# zeta2rework_lw_v27_rework.net
KiCad netlist of a schematic drawn in EAGLE
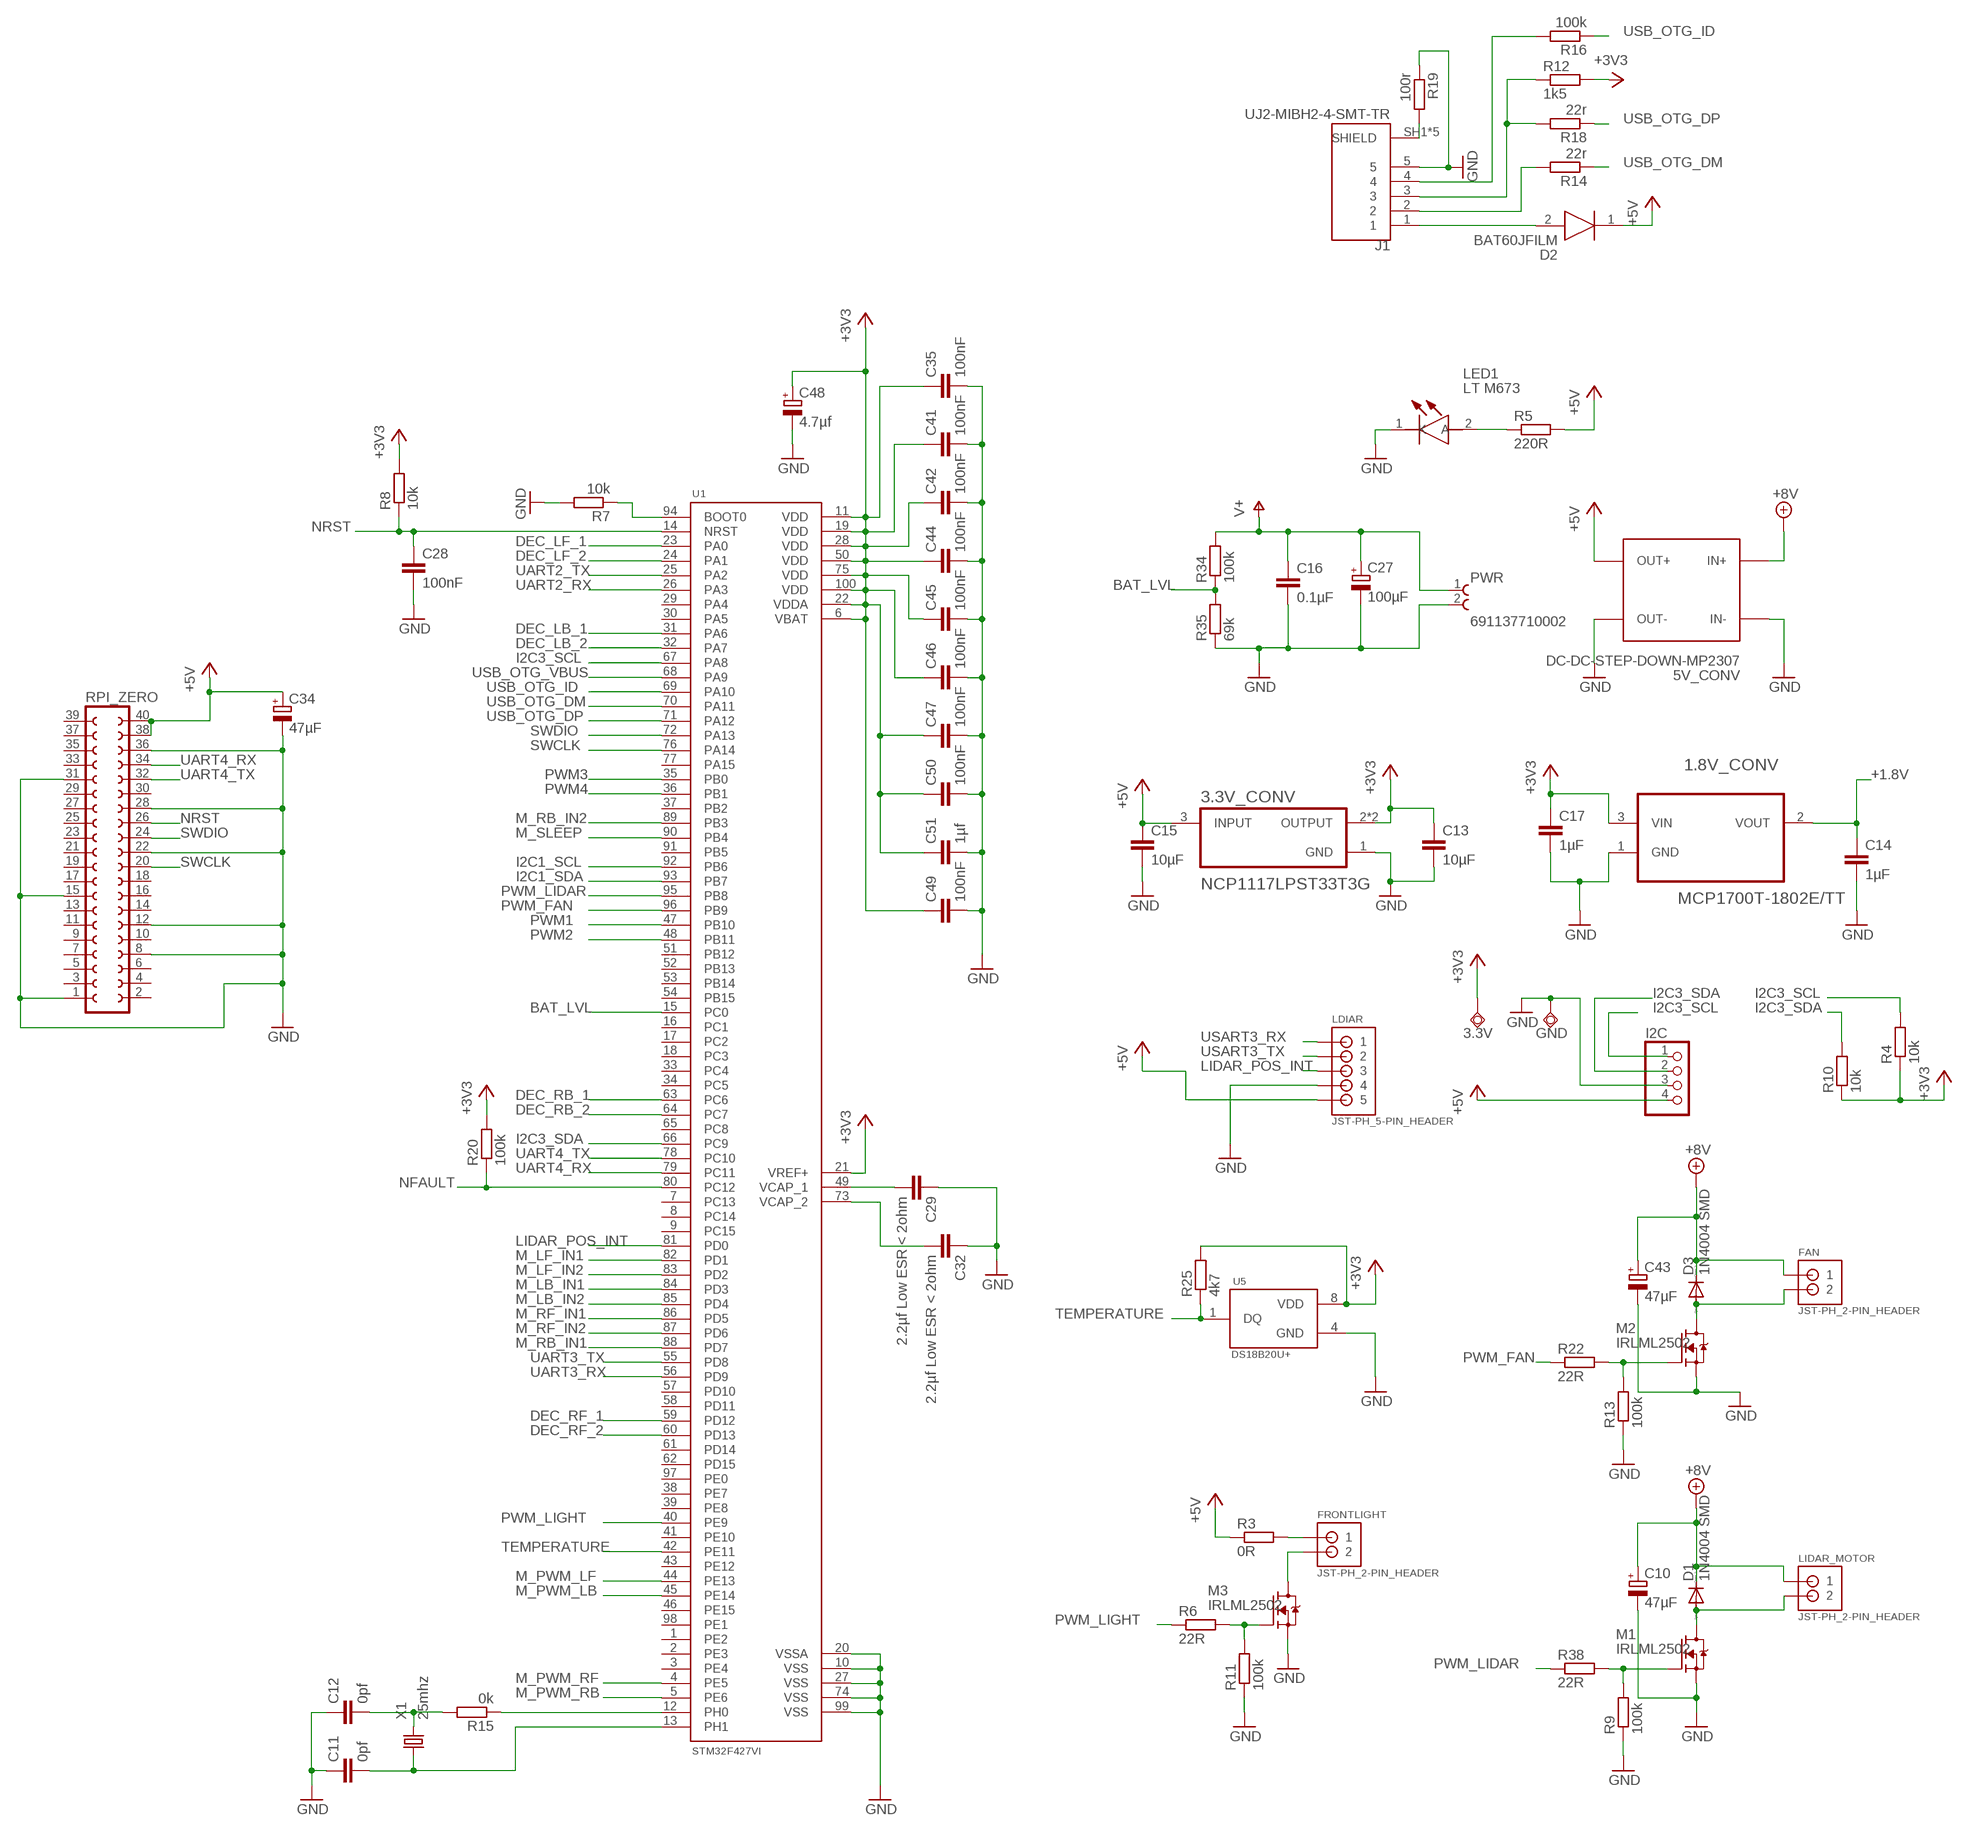
[diagram p0: schematic, sheet 1, part 1 of 2]
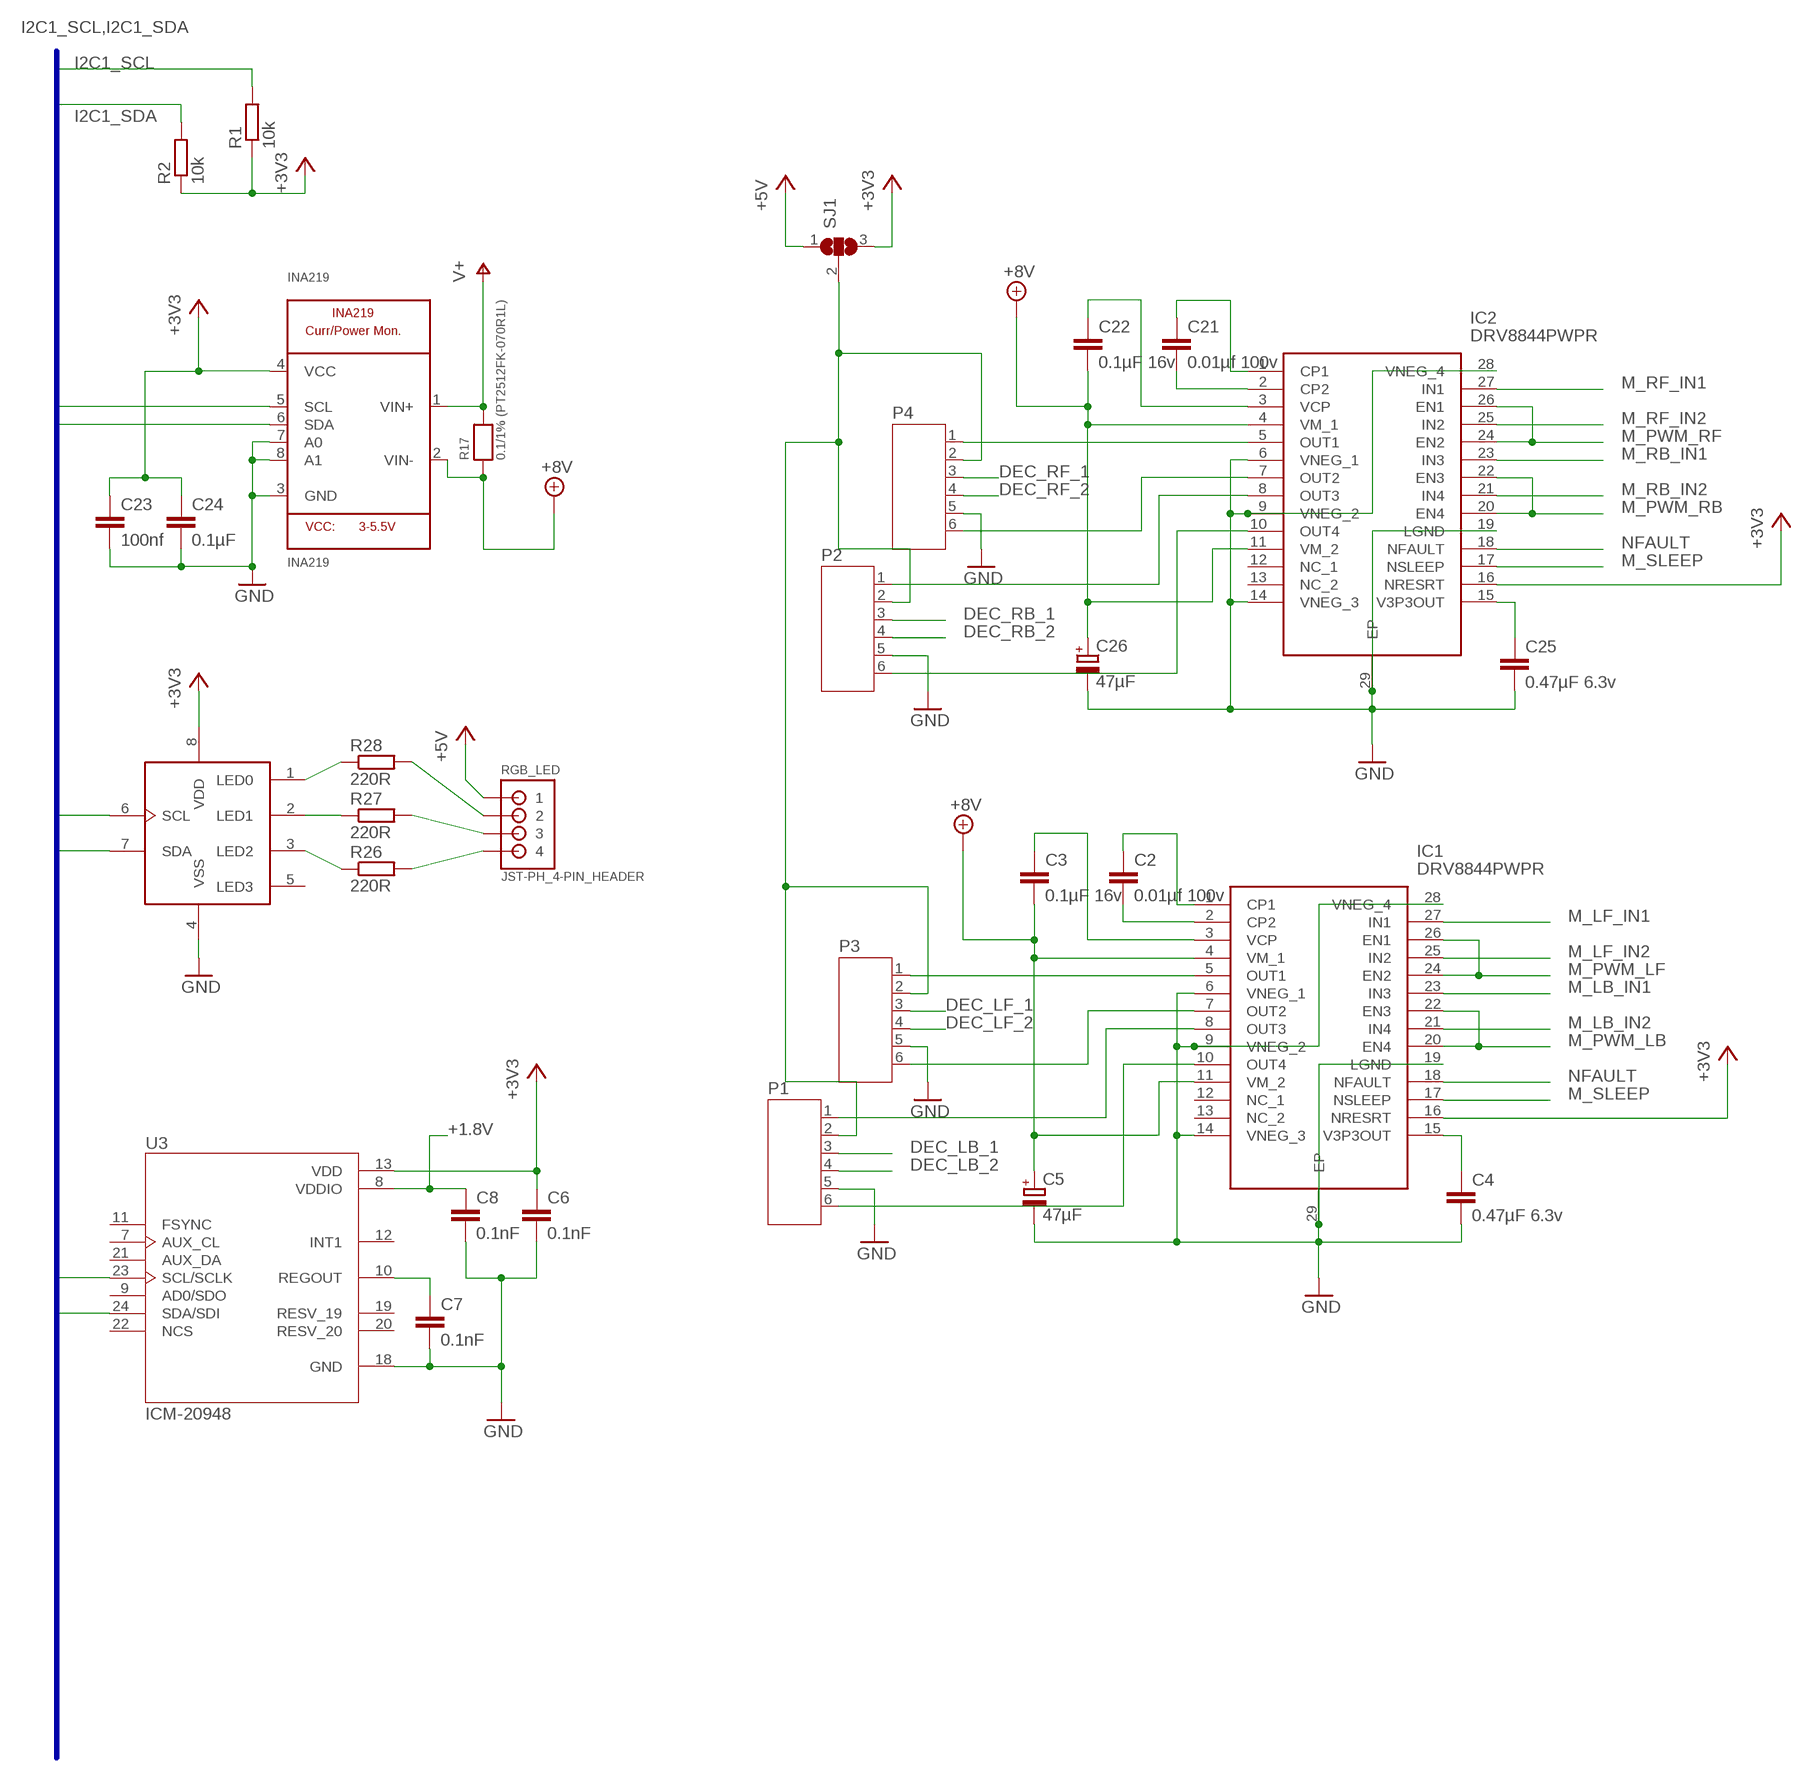
[diagram p1: schematic, sheet 1, part 2 of 2]

(export (version "E")
  (design (tool "Eeschema 10.0.6"))
  (components
    (comp (ref "1.8V_CONV")
      (value "MCP1700T-1802E/TT")
      (footprint "eagle-import:SOT95P237X112-3N")
      (fields (field (name "MF") "Microchip") (field (name "MP") "MCP1700T-2102E/TT"))
      (libsource (lib "eagle-import") (part "MCP1700T-2102E/TT"))
    )
    (comp (ref "3.3V")
      (value "TPSQTP20R")
      (footprint "eagle-import:TP20R")
      (libsource (lib "eagle-import") (part "TPSQTP20R"))
    )
    (comp (ref "3.3V_CONV")
      (value "NCP1117LPST33T3G")
      (footprint "eagle-import:SOT230P700X175-4N")
      (fields (field (name "MF") "ON Semiconductor"))
      (libsource (lib "eagle-import") (part "NCP1117LPST33T3G"))
    )
    (comp (ref "5V_CONV")
      (value "DC-DC-STEP-DOWN-MP2307")
      (footprint "eagle-import:DC-DC-STEP-DOWN-MP2307")
      (libsource (lib "eagle-import") (part "DC-DC-STEP-DOWN-MP2307"))
    )
    (comp (ref "C2")
      (value "0.01µf 100v")
      (footprint "eagle-import:C1206")
      (libsource (lib "eagle-import") (part "C-EUC1206"))
    )
    (comp (ref "C3")
      (value "0.1µF 16v")
      (footprint "eagle-import:C1206")
      (libsource (lib "eagle-import") (part "C-EUC1206"))
    )
    (comp (ref "C4")
      (value "0.47µF 6.3v")
      (footprint "eagle-import:C1206")
      (libsource (lib "eagle-import") (part "C-EUC1206"))
    )
    (comp (ref "C5")
      (value "47µF")
      (footprint "eagle-import:UD-5X5,8_NICHICON")
      (libsource (lib "eagle-import") (part "CPOL-EUUD-5X5,8"))
    )
    (comp (ref "C6")
      (value "0.1nF")
      (footprint "eagle-import:C0603")
      (libsource (lib "eagle-import") (part "C-EUC0603"))
    )
    (comp (ref "C7")
      (value "0.1nF")
      (footprint "eagle-import:C1206")
      (libsource (lib "eagle-import") (part "C-EUC1206"))
    )
    (comp (ref "C8")
      (value "0.1nF")
      (footprint "eagle-import:C1206")
      (libsource (lib "eagle-import") (part "C-EUC1206"))
    )
    (comp (ref "C10")
      (value "47µF")
      (footprint "eagle-import:UD-5X5,8_NICHICON")
      (libsource (lib "eagle-import") (part "CPOL-EUUD-5X5,8"))
    )
    (comp (ref "C11")
      (value "0pf")
      (footprint "eagle-import:C1206")
      (libsource (lib "eagle-import") (part "C-EUC1206"))
    )
    (comp (ref "C12")
      (value "0pf")
      (footprint "eagle-import:C1206")
      (libsource (lib "eagle-import") (part "C-EUC1206"))
    )
    (comp (ref "C13")
      (value "10µF")
      (footprint "eagle-import:C1206")
      (libsource (lib "eagle-import") (part "C-EUC1206"))
    )
    (comp (ref "C14")
      (value "1µF")
      (footprint "eagle-import:C1206")
      (libsource (lib "eagle-import") (part "C-EUC1206"))
    )
    (comp (ref "C15")
      (value "10µF")
      (footprint "eagle-import:C1206")
      (libsource (lib "eagle-import") (part "C-EUC1206"))
    )
    (comp (ref "C16")
      (value "0.1µF")
      (footprint "eagle-import:C1206")
      (libsource (lib "eagle-import") (part "C-EUC1206"))
    )
    (comp (ref "C17")
      (value "1µF")
      (footprint "eagle-import:C1206")
      (libsource (lib "eagle-import") (part "C-EUC1206"))
    )
    (comp (ref "C21")
      (value "0.01µf 100v")
      (footprint "eagle-import:C1206")
      (libsource (lib "eagle-import") (part "C-EUC1206"))
    )
    (comp (ref "C22")
      (value "0.1µF 16v")
      (footprint "eagle-import:C1206")
      (libsource (lib "eagle-import") (part "C-EUC1206"))
    )
    (comp (ref "C23")
      (value "100nf")
      (footprint "eagle-import:C1206")
      (libsource (lib "eagle-import") (part "C-EUC1206"))
    )
    (comp (ref "C24")
      (value "0.1µF")
      (footprint "eagle-import:C1206")
      (libsource (lib "eagle-import") (part "C-EUC1206"))
    )
    (comp (ref "C25")
      (value "0.47µF 6.3v")
      (footprint "eagle-import:C1206")
      (libsource (lib "eagle-import") (part "C-EUC1206"))
    )
    (comp (ref "C26")
      (value "47µF")
      (footprint "eagle-import:UD-5X5,8_NICHICON")
      (libsource (lib "eagle-import") (part "CPOL-EUUD-5X5,8"))
    )
    (comp (ref "C27")
      (value "100µF")
      (footprint "eagle-import:UD-5X5,8_NICHICON")
      (libsource (lib "eagle-import") (part "CPOL-EUUD-5X5,8"))
    )
    (comp (ref "C28")
      (value "100nF")
      (footprint "eagle-import:C1206")
      (libsource (lib "eagle-import") (part "C-EUC1206"))
    )
    (comp (ref "C29")
      (value "2.2µf Low ESR < 2ohm")
      (footprint "eagle-import:C1206")
      (libsource (lib "eagle-import") (part "C-EUC1206"))
    )
    (comp (ref "C32")
      (value "2.2µf Low ESR < 2ohm")
      (footprint "eagle-import:C1206")
      (libsource (lib "eagle-import") (part "C-EUC1206"))
    )
    (comp (ref "C34")
      (value "47µF")
      (footprint "eagle-import:UD-5X5,8_NICHICON")
      (libsource (lib "eagle-import") (part "CPOL-EUUD-5X5,8"))
    )
    (comp (ref "C35")
      (value "100nF")
      (footprint "eagle-import:C1206")
      (libsource (lib "eagle-import") (part "C-EUC1206"))
    )
    (comp (ref "C41")
      (value "100nF")
      (footprint "eagle-import:C1206")
      (libsource (lib "eagle-import") (part "C-EUC1206"))
    )
    (comp (ref "C42")
      (value "100nF")
      (footprint "eagle-import:C1206")
      (libsource (lib "eagle-import") (part "C-EUC1206"))
    )
    (comp (ref "C43")
      (value "47µF")
      (footprint "eagle-import:UD-5X5,8_NICHICON")
      (libsource (lib "eagle-import") (part "CPOL-EUUD-5X5,8"))
    )
    (comp (ref "C44")
      (value "100nF")
      (footprint "eagle-import:C1206")
      (libsource (lib "eagle-import") (part "C-EUC1206"))
    )
    (comp (ref "C45")
      (value "100nF")
      (footprint "eagle-import:C1206")
      (libsource (lib "eagle-import") (part "C-EUC1206"))
    )
    (comp (ref "C46")
      (value "100nF")
      (footprint "eagle-import:C1206")
      (libsource (lib "eagle-import") (part "C-EUC1206"))
    )
    (comp (ref "C47")
      (value "100nF")
      (footprint "eagle-import:C1206")
      (libsource (lib "eagle-import") (part "C-EUC1206"))
    )
    (comp (ref "C48")
      (value "4.7µf")
      (footprint "eagle-import:SMC_P")
      (libsource (lib "eagle-import") (part "CPOL-EUSMCP"))
    )
    (comp (ref "C49")
      (value "100nF")
      (footprint "eagle-import:C1206")
      (libsource (lib "eagle-import") (part "C-EUC1206"))
    )
    (comp (ref "C50")
      (value "100nF")
      (footprint "eagle-import:C1206")
      (libsource (lib "eagle-import") (part "C-EUC1206"))
    )
    (comp (ref "C51")
      (value "1µf")
      (footprint "eagle-import:C1206")
      (libsource (lib "eagle-import") (part "C-EUC1206"))
    )
    (comp (ref "D1")
      (value "1N4004 SMD")
      (footprint "eagle-import:DO214AC")
      (libsource (lib "eagle-import") (part "DIODE-DO214AC"))
    )
    (comp (ref "D2")
      (value "BAT60JFILM")
      (footprint "eagle-import:SOD2513X117N")
      (fields (field (name "MOUSER_PART_NUMBER") "511-BAT60JFILM") (field (name "RS_PART_NUMBER") "1458781"))
      (libsource (lib "eagle-import") (part "BAT60JFILM"))
    )
    (comp (ref "D3")
      (value "1N4004 SMD")
      (footprint "eagle-import:DO214AC")
      (libsource (lib "eagle-import") (part "DIODE-DO214AC"))
    )
    (comp (ref "FAN")
      (value "JST-PH_2-PIN_HEADER")
      (footprint "eagle-import:JST_B2B-PH_HEADER")
      (libsource (lib "eagle-import") (part "JST-PH_2-PIN_HEADER"))
    )
    (comp (ref "FRONTLIGHT")
      (value "JST-PH_2-PIN_HEADER")
      (footprint "eagle-import:JST_B2B-PH_HEADER")
      (libsource (lib "eagle-import") (part "JST-PH_2-PIN_HEADER"))
    )
    (comp (ref "GND")
      (value "TPSQTP20R")
      (footprint "eagle-import:TP20R")
      (libsource (lib "eagle-import") (part "TPSQTP20R"))
    )
    (comp (ref "I2C")
      (value "PINHD-1X4")
      (footprint "eagle-import:1X04")
      (libsource (lib "eagle-import") (part "PINHD-1X4"))
    )
    (comp (ref "IC1")
      (value "DRV8844PWPR")
      (footprint "eagle-import:SOP65P640X120-29N")
      (fields (field (name "MOUSER_PART_NUMBER") "595-DRV8844PWPR"))
      (libsource (lib "eagle-import") (part "DRV8844PWPR"))
    )
    (comp (ref "IC2")
      (value "DRV8844PWPR")
      (footprint "eagle-import:SOP65P640X120-29N")
      (fields (field (name "MOUSER_PART_NUMBER") "595-DRV8844PWPR"))
      (libsource (lib "eagle-import") (part "DRV8844PWPR"))
    )
    (comp (ref "INA219")
      (value "INA219")
      (footprint "eagle-import:SOT23-8")
      (fields (field (name "MF") "Texas Instruments"))
      (libsource (lib "eagle-import") (part "INA219"))
    )
    (comp (ref "J1")
      (value "UJ2-MIBH2-4-SMT-TR")
      (footprint "eagle-import:CUI_UJ2-MIBH2-4-SMT-TR")
      (fields (field (name "MF") "CUI Inc."))
      (libsource (lib "eagle-import") (part "UJ2-MIBH2-4-SMT-TR"))
    )
    (comp (ref "LDIAR")
      (value "JST-PH_5-PIN_HEADER")
      (footprint "eagle-import:JST_B5B-PH_HEADER")
      (libsource (lib "eagle-import") (part "JST-PH_5-PIN_HEADER"))
    )
    (comp (ref "LED1")
      (value "LT M673")
      (footprint "eagle-import:LTM673-N1R2-25")
      (fields
        (field (name "MANUFACTURER_PART_NUMBER") "LT M673-N1R2-25")
        (field (name "MOUSER_PART_NUMBER") "720-LTM673N1R225Z")
        (field (name "RS_PART_NUMBER") "9133231")
      )
      (libsource (lib "eagle-import") (part "LT_M673-N1R2-25"))
    )
    (comp (ref "LIDAR_MOTOR")
      (value "JST-PH_2-PIN_HEADER")
      (footprint "eagle-import:JST_B2B-PH_HEADER")
      (libsource (lib "eagle-import") (part "JST-PH_2-PIN_HEADER"))
    )
    (comp (ref "M1")
      (value "IRLML2502")
      (footprint "eagle-import:SOT23")
      (fields (field (name "MF") "Infineon") (field (name "MP") "IRLML2502TRPBF"))
      (libsource (lib "eagle-import") (part "IRLML2502TRPBF"))
    )
    (comp (ref "M2")
      (value "IRLML2502")
      (footprint "eagle-import:SOT23")
      (fields (field (name "MF") "Infineon") (field (name "MP") "IRLML2502TRPBF"))
      (libsource (lib "eagle-import") (part "IRLML2502TRPBF"))
    )
    (comp (ref "M3")
      (value "IRLML2502")
      (footprint "eagle-import:SOT23")
      (fields (field (name "MF") "Infineon") (field (name "MP") "IRLML2502TRPBF"))
      (libsource (lib "eagle-import") (part "IRLML2502TRPBF"))
    )
    (comp (ref "P1")
      (value "JST-PH6")
      (footprint "eagle-import:JST-PH6")
      (libsource (lib "eagle-import") (part "JST-PH6"))
    )
    (comp (ref "P2")
      (value "JST-PH6")
      (footprint "eagle-import:JST-PH6")
      (libsource (lib "eagle-import") (part "JST-PH6"))
    )
    (comp (ref "P3")
      (value "JST-PH6")
      (footprint "eagle-import:JST-PH6")
      (libsource (lib "eagle-import") (part "JST-PH6"))
    )
    (comp (ref "P4")
      (value "JST-PH6")
      (footprint "eagle-import:JST-PH6")
      (libsource (lib "eagle-import") (part "JST-PH6"))
    )
    (comp (ref "PCA9533")
      (value "PCA9533")
      (footprint "eagle-import:SOIC8")
      (libsource (lib "eagle-import") (part "PCA9533"))
    )
    (comp (ref "PWR")
      (value "691137710002")
      (footprint "eagle-import:691137710002")
      (fields (field (name "MF") "Wurth Electronics"))
      (libsource (lib "eagle-import") (part "691137710002"))
    )
    (comp (ref "R1")
      (value "10k")
      (footprint "eagle-import:R0603")
      (libsource (lib "eagle-import") (part "R-EU_R0603"))
    )
    (comp (ref "R2")
      (value "10k")
      (footprint "eagle-import:R0603")
      (libsource (lib "eagle-import") (part "R-EU_R0603"))
    )
    (comp (ref "R3")
      (value "0R")
      (footprint "eagle-import:R0603")
      (libsource (lib "eagle-import") (part "R-EU_R0603"))
    )
    (comp (ref "R4")
      (value "10k")
      (footprint "eagle-import:R0603")
      (libsource (lib "eagle-import") (part "R-EU_R0603"))
    )
    (comp (ref "R5")
      (value "220R")
      (footprint "eagle-import:R0603")
      (libsource (lib "eagle-import") (part "R-EU_R0603"))
    )
    (comp (ref "R6")
      (value "22R")
      (footprint "eagle-import:R0603")
      (libsource (lib "eagle-import") (part "R-EU_R0603"))
    )
    (comp (ref "R7")
      (value "10k")
      (footprint "eagle-import:R0603")
      (libsource (lib "eagle-import") (part "R-EU_R0603"))
    )
    (comp (ref "R8")
      (value "10k")
      (footprint "eagle-import:R0603")
      (libsource (lib "eagle-import") (part "R-EU_R0603"))
    )
    (comp (ref "R9")
      (value "100k")
      (footprint "eagle-import:R0603")
      (libsource (lib "eagle-import") (part "R-EU_R0603"))
    )
    (comp (ref "R10")
      (value "10k")
      (footprint "eagle-import:R0603")
      (libsource (lib "eagle-import") (part "R-EU_R0603"))
    )
    (comp (ref "R11")
      (value "100k")
      (footprint "eagle-import:R0603")
      (libsource (lib "eagle-import") (part "R-EU_R0603"))
    )
    (comp (ref "R12")
      (value "1k5")
      (footprint "eagle-import:R0603")
      (libsource (lib "eagle-import") (part "R-EU_R0603"))
    )
    (comp (ref "R13")
      (value "100k")
      (footprint "eagle-import:R0603")
      (libsource (lib "eagle-import") (part "R-EU_R0603"))
    )
    (comp (ref "R14")
      (value "22r")
      (footprint "eagle-import:R0603")
      (libsource (lib "eagle-import") (part "R-EU_R0603"))
    )
    (comp (ref "R15")
      (value "0k")
      (footprint "eagle-import:R0603")
      (libsource (lib "eagle-import") (part "R-EU_R0603"))
    )
    (comp (ref "R16")
      (value "100k")
      (footprint "eagle-import:R0603")
      (libsource (lib "eagle-import") (part "R-EU_R0603"))
    )
    (comp (ref "R17")
      (value "0.1/1% (PT2512FK-070R1L)")
      (footprint "eagle-import:2512")
      (libsource (lib "eagle-import") (part "RESISTOR2512"))
    )
    (comp (ref "R18")
      (value "22r")
      (footprint "eagle-import:R0603")
      (libsource (lib "eagle-import") (part "R-EU_R0603"))
    )
    (comp (ref "R19")
      (value "100r")
      (footprint "eagle-import:R0603")
      (libsource (lib "eagle-import") (part "R-EU_R0603"))
    )
    (comp (ref "R20")
      (value "100k")
      (footprint "eagle-import:R0603")
      (libsource (lib "eagle-import") (part "R-EU_R0603"))
    )
    (comp (ref "R22")
      (value "22R")
      (footprint "eagle-import:R0603")
      (libsource (lib "eagle-import") (part "R-EU_R0603"))
    )
    (comp (ref "R25")
      (value "4k7")
      (footprint "eagle-import:R0603")
      (libsource (lib "eagle-import") (part "R-EU_R0603"))
    )
    (comp (ref "R26")
      (value "220R")
      (footprint "eagle-import:R0603")
      (libsource (lib "eagle-import") (part "R-EU_R0603"))
    )
    (comp (ref "R27")
      (value "220R")
      (footprint "eagle-import:R0603")
      (libsource (lib "eagle-import") (part "R-EU_R0603"))
    )
    (comp (ref "R28")
      (value "220R")
      (footprint "eagle-import:R0603")
      (libsource (lib "eagle-import") (part "R-EU_R0603"))
    )
    (comp (ref "R34")
      (value "100k")
      (footprint "eagle-import:R0603")
      (libsource (lib "eagle-import") (part "R-EU_R0603"))
    )
    (comp (ref "R35")
      (value "69k")
      (footprint "eagle-import:R0603")
      (libsource (lib "eagle-import") (part "R-EU_R0603"))
    )
    (comp (ref "R38")
      (value "22R")
      (footprint "eagle-import:R0603")
      (libsource (lib "eagle-import") (part "R-EU_R0603"))
    )
    (comp (ref "RGB_LED")
      (value "JST-PH_4-PIN_HEADER")
      (footprint "eagle-import:JST_B4B-PH_HEADER")
      (libsource (lib "eagle-import") (part "JST-PH_4-PIN_HEADER"))
    )
    (comp (ref "RPI_ZERO")
      (value "FE20-2")
      (footprint "eagle-import:FE20-2")
      (libsource (lib "eagle-import") (part "FE20-2"))
    )
    (comp (ref "SJ1")
      (value "SJ2W")
      (footprint "eagle-import:SJ_2")
      (libsource (lib "eagle-import") (part "SJ2W"))
    )
    (comp (ref "U1")
      (value "STM32F427VI")
      (footprint "eagle-import:QFP50P1600X1600X160-100N")
      (fields (field (name "MF") "STMicroelectronics") (field (name "MP") "STM32F427VGT7"))
      (libsource (lib "eagle-import") (part "STM32F427VGT7"))
    )
    (comp (ref "U3")
      (value "ICM-20948")
      (footprint "eagle-import:QFN40P300X300X105-25N")
      (fields (field (name "MF") "TDK InvenSense"))
      (libsource (lib "eagle-import") (part "ICM-20948"))
    )
    (comp (ref "U5")
      (value "DS18B20U+")
      (footprint "eagle-import:SOP65P490X95-8N")
      (fields (field (name "MF") "Maxim"))
      (libsource (lib "eagle-import") (part "DS18B20U+"))
    )
    (comp (ref "X1")
      (value "25mhz")
      (footprint "eagle-import:5.0X3.2_KX-9A")
      (libsource (lib "eagle-import") (part "KX-9A"))
    )
  )
  (nets
    (net (code "1") (name "+3V3") (class "Default")
      (node (ref "1.8V_CONV") (pin "3") (pinfunction "VIN_3") (pintype "input"))
      (node (ref "3.3V") (pin "TP") (pinfunction "TP_TP") (pintype "input"))
      (node (ref "3.3V_CONV") (pin "2") (pinfunction "OUTPUT_2") (pintype "output"))
      (node (ref "3.3V_CONV") (pin "4") (pinfunction "OUTPUT_4") (pintype "output"))
      (node (ref "C13") (pin "1") (pinfunction "1_1") (pintype "passive"))
      (node (ref "C17") (pin "1") (pinfunction "1_1") (pintype "passive"))
      (node (ref "C23") (pin "1") (pinfunction "1_1") (pintype "passive"))
      (node (ref "C24") (pin "1") (pinfunction "1_1") (pintype "passive"))
      (node (ref "C35") (pin "1") (pinfunction "1_1") (pintype "passive"))
      (node (ref "C41") (pin "1") (pinfunction "1_1") (pintype "passive"))
      (node (ref "C42") (pin "1") (pinfunction "1_1") (pintype "passive"))
      (node (ref "C44") (pin "1") (pinfunction "1_1") (pintype "passive"))
      (node (ref "C45") (pin "1") (pinfunction "1_1") (pintype "passive"))
      (node (ref "C46") (pin "1") (pinfunction "1_1") (pintype "passive"))
      (node (ref "C47") (pin "1") (pinfunction "1_1") (pintype "passive"))
      (node (ref "C48") (pin "+") (pinfunction "+_+") (pintype "passive"))
      (node (ref "C49") (pin "1") (pinfunction "1_1") (pintype "passive"))
      (node (ref "C50") (pin "1") (pinfunction "1_1") (pintype "passive"))
      (node (ref "C51") (pin "1") (pinfunction "1_1") (pintype "passive"))
      (node (ref "C6") (pin "1") (pinfunction "1_1") (pintype "passive"))
      (node (ref "IC1") (pin "16") (pinfunction "NRESRT_16") (pintype "bidirectional"))
      (node (ref "IC2") (pin "16") (pinfunction "NRESRT_16") (pintype "bidirectional"))
      (node (ref "INA219") (pin "4") (pinfunction "VCC_4") (pintype "bidirectional"))
      (node (ref "PCA9533") (pin "8") (pinfunction "VDD_8") (pintype "power_in"))
      (node (ref "R1") (pin "1") (pinfunction "1_1") (pintype "passive"))
      (node (ref "R10") (pin "1") (pinfunction "1_1") (pintype "passive"))
      (node (ref "R12") (pin "2") (pinfunction "2_2") (pintype "passive"))
      (node (ref "R2") (pin "1") (pinfunction "1_1") (pintype "passive"))
      (node (ref "R20") (pin "2") (pinfunction "2_2") (pintype "passive"))
      (node (ref "R25") (pin "2") (pinfunction "2_2") (pintype "passive"))
      (node (ref "R4") (pin "1") (pinfunction "1_1") (pintype "passive"))
      (node (ref "R8") (pin "2") (pinfunction "2_2") (pintype "passive"))
      (node (ref "SJ1") (pin "3") (pinfunction "3_3") (pintype "passive"))
      (node (ref "U1") (pin "100") (pinfunction "VDD_100") (pintype "power_in"))
      (node (ref "U1") (pin "11") (pinfunction "VDD_11") (pintype "power_in"))
      (node (ref "U1") (pin "19") (pinfunction "VDD_19") (pintype "power_in"))
      (node (ref "U1") (pin "21") (pinfunction "VREF+_21") (pintype "power_in"))
      (node (ref "U1") (pin "22") (pinfunction "VDDA_22") (pintype "power_in"))
      (node (ref "U1") (pin "28") (pinfunction "VDD_28") (pintype "power_in"))
      (node (ref "U1") (pin "50") (pinfunction "VDD_50") (pintype "power_in"))
      (node (ref "U1") (pin "6") (pinfunction "VBAT_6") (pintype "power_in"))
      (node (ref "U1") (pin "75") (pinfunction "VDD_75") (pintype "power_in"))
      (node (ref "U3") (pin "13") (pinfunction "VDD_13") (pintype "power_in"))
      (node (ref "U5") (pin "8") (pinfunction "VDD_8") (pintype "power_in"))
    )
    (net (code "2") (name "+5V") (class "Default")
      (node (ref "3.3V_CONV") (pin "3") (pinfunction "INPUT_3") (pintype "input"))
      (node (ref "5V_CONV") (pin "OUT+") (pinfunction "OUT+_OUT+") (pintype "bidirectional"))
      (node (ref "C15") (pin "1") (pinfunction "1_1") (pintype "passive"))
      (node (ref "C34") (pin "+") (pinfunction "+_+") (pintype "passive"))
      (node (ref "D2") (pin "1") (pinfunction "K_1") (pintype "bidirectional"))
      (node (ref "I2C") (pin "4") (pinfunction "4_4") (pintype "passive"))
      (node (ref "LDIAR") (pin "P5") (pinfunction "5_P5") (pintype "bidirectional"))
      (node (ref "R3") (pin "1") (pinfunction "1_1") (pintype "passive"))
      (node (ref "R5") (pin "2") (pinfunction "2_2") (pintype "passive"))
      (node (ref "RGB_LED") (pin "P1") (pinfunction "1_P1") (pintype "bidirectional"))
      (node (ref "RPI_ZERO") (pin "38") (pinfunction "38_38") (pintype "passive"))
      (node (ref "RPI_ZERO") (pin "40") (pinfunction "40_40") (pintype "passive"))
      (node (ref "SJ1") (pin "1") (pinfunction "1_1") (pintype "passive"))
    )
    (net (code "3") (name "+8V") (class "Default")
      (node (ref "5V_CONV") (pin "IN+") (pinfunction "IN+_IN+") (pintype "bidirectional"))
      (node (ref "C10") (pin "+") (pinfunction "+_+") (pintype "passive"))
      (node (ref "C22") (pin "2") (pinfunction "2_2") (pintype "passive"))
      (node (ref "C26") (pin "+") (pinfunction "+_+") (pintype "passive"))
      (node (ref "C3") (pin "2") (pinfunction "2_2") (pintype "passive"))
      (node (ref "C43") (pin "+") (pinfunction "+_+") (pintype "passive"))
      (node (ref "C5") (pin "+") (pinfunction "+_+") (pintype "passive"))
      (node (ref "D1") (pin "C") (pinfunction "C_C") (pintype "passive"))
      (node (ref "D3") (pin "C") (pinfunction "C_C") (pintype "passive"))
      (node (ref "FAN") (pin "P1") (pinfunction "1_P1") (pintype "bidirectional"))
      (node (ref "IC1") (pin "11") (pinfunction "VM_2_11") (pintype "bidirectional"))
      (node (ref "IC1") (pin "4") (pinfunction "VM_1_4") (pintype "bidirectional"))
      (node (ref "IC2") (pin "11") (pinfunction "VM_2_11") (pintype "bidirectional"))
      (node (ref "IC2") (pin "4") (pinfunction "VM_1_4") (pintype "bidirectional"))
      (node (ref "INA219") (pin "2") (pinfunction "VIN-_2") (pintype "bidirectional"))
      (node (ref "LIDAR_MOTOR") (pin "P1") (pinfunction "1_P1") (pintype "bidirectional"))
      (node (ref "R17") (pin "1") (pinfunction "1_1") (pintype "passive"))
    )
    (net (code "4") (name "/+1.8V") (class "Default")
      (node (ref "1.8V_CONV") (pin "2") (pinfunction "VOUT_2") (pintype "output"))
      (node (ref "C14") (pin "1") (pinfunction "1_1") (pintype "passive"))
      (node (ref "C8") (pin "1") (pinfunction "1_1") (pintype "passive"))
      (node (ref "U3") (pin "8") (pinfunction "VDDIO_8") (pintype "power_in"))
    )
    (net (code "5") (name "/BAT_LVL") (class "Default")
      (node (ref "R34") (pin "1") (pinfunction "1_1") (pintype "passive"))
      (node (ref "R35") (pin "2") (pinfunction "2_2") (pintype "passive"))
      (node (ref "U1") (pin "15") (pinfunction "PC0_15") (pintype "bidirectional"))
    )
    (net (code "6") (name "/DEC_LB_1") (class "Default")
      (node (ref "P1") (pin "3") (pinfunction "3_3") (pintype "passive"))
      (node (ref "U1") (pin "31") (pinfunction "PA6_31") (pintype "bidirectional"))
    )
    (net (code "7") (name "/DEC_LB_2") (class "Default")
      (node (ref "P1") (pin "4") (pinfunction "4_4") (pintype "passive"))
      (node (ref "U1") (pin "32") (pinfunction "PA7_32") (pintype "bidirectional"))
    )
    (net (code "8") (name "/DEC_LF_1") (class "Default")
      (node (ref "P3") (pin "3") (pinfunction "3_3") (pintype "passive"))
      (node (ref "U1") (pin "23") (pinfunction "PA0_23") (pintype "bidirectional"))
    )
    (net (code "9") (name "/DEC_LF_2") (class "Default")
      (node (ref "P3") (pin "4") (pinfunction "4_4") (pintype "passive"))
      (node (ref "U1") (pin "24") (pinfunction "PA1_24") (pintype "bidirectional"))
    )
    (net (code "10") (name "/DEC_RB_1") (class "Default")
      (node (ref "P2") (pin "3") (pinfunction "3_3") (pintype "passive"))
      (node (ref "U1") (pin "63") (pinfunction "PC6_63") (pintype "bidirectional"))
    )
    (net (code "11") (name "/DEC_RB_2") (class "Default")
      (node (ref "P2") (pin "4") (pinfunction "4_4") (pintype "passive"))
      (node (ref "U1") (pin "64") (pinfunction "PC7_64") (pintype "bidirectional"))
    )
    (net (code "12") (name "/DEC_RF_1") (class "Default")
      (node (ref "P4") (pin "3") (pinfunction "3_3") (pintype "passive"))
      (node (ref "U1") (pin "59") (pinfunction "PD12_59") (pintype "bidirectional"))
    )
    (net (code "13") (name "/DEC_RF_2") (class "Default")
      (node (ref "P4") (pin "4") (pinfunction "4_4") (pintype "passive"))
      (node (ref "U1") (pin "60") (pinfunction "PD13_60") (pintype "bidirectional"))
    )
    (net (code "14") (name "/I2C1_SCL") (class "Default")
      (node (ref "INA219") (pin "5") (pinfunction "SCL_5") (pintype "bidirectional"))
      (node (ref "PCA9533") (pin "6") (pinfunction "SCL_6") (pintype "input"))
      (node (ref "R1") (pin "2") (pinfunction "2_2") (pintype "passive"))
      (node (ref "U1") (pin "92") (pinfunction "PB6_92") (pintype "bidirectional"))
      (node (ref "U3") (pin "23") (pinfunction "SCL/SCLK_23") (pintype "input"))
    )
    (net (code "15") (name "/I2C1_SDA") (class "Default")
      (node (ref "INA219") (pin "6") (pinfunction "SDA_6") (pintype "bidirectional"))
      (node (ref "PCA9533") (pin "7") (pinfunction "SDA_7") (pintype "bidirectional"))
      (node (ref "R2") (pin "2") (pinfunction "2_2") (pintype "passive"))
      (node (ref "U1") (pin "93") (pinfunction "PB7_93") (pintype "bidirectional"))
      (node (ref "U3") (pin "24") (pinfunction "SDA/SDI_24") (pintype "bidirectional"))
    )
    (net (code "16") (name "/I2C3_SCL") (class "Default")
      (node (ref "I2C") (pin "1") (pinfunction "1_1") (pintype "passive"))
      (node (ref "R4") (pin "2") (pinfunction "2_2") (pintype "passive"))
      (node (ref "U1") (pin "67") (pinfunction "PA8_67") (pintype "bidirectional"))
    )
    (net (code "17") (name "/I2C3_SDA") (class "Default")
      (node (ref "I2C") (pin "2") (pinfunction "2_2") (pintype "passive"))
      (node (ref "R10") (pin "2") (pinfunction "2_2") (pintype "passive"))
      (node (ref "U1") (pin "66") (pinfunction "PC9_66") (pintype "bidirectional"))
    )
    (net (code "18") (name "/LIDAR_POS_INT") (class "Default")
      (node (ref "LDIAR") (pin "P3") (pinfunction "3_P3") (pintype "bidirectional"))
      (node (ref "U1") (pin "81") (pinfunction "PD0_81") (pintype "bidirectional"))
    )
    (net (code "19") (name "/M_LB_IN1") (class "Default")
      (node (ref "IC1") (pin "23") (pinfunction "IN3_23") (pintype "input"))
      (node (ref "U1") (pin "84") (pinfunction "PD3_84") (pintype "bidirectional"))
    )
    (net (code "20") (name "/M_LB_IN2") (class "Default")
      (node (ref "IC1") (pin "21") (pinfunction "IN4_21") (pintype "input"))
      (node (ref "U1") (pin "85") (pinfunction "PD4_85") (pintype "bidirectional"))
    )
    (net (code "21") (name "/M_LF_IN1") (class "Default")
      (node (ref "IC1") (pin "27") (pinfunction "IN1_27") (pintype "input"))
      (node (ref "U1") (pin "82") (pinfunction "PD1_82") (pintype "bidirectional"))
    )
    (net (code "22") (name "/M_LF_IN2") (class "Default")
      (node (ref "IC1") (pin "25") (pinfunction "IN2_25") (pintype "input"))
      (node (ref "U1") (pin "83") (pinfunction "PD2_83") (pintype "bidirectional"))
    )
    (net (code "23") (name "/M_PWM_LB") (class "Default")
      (node (ref "IC1") (pin "20") (pinfunction "EN4_20") (pintype "bidirectional"))
      (node (ref "IC1") (pin "22") (pinfunction "EN3_22") (pintype "bidirectional"))
      (node (ref "U1") (pin "45") (pinfunction "PE14_45") (pintype "bidirectional"))
    )
    (net (code "24") (name "/M_PWM_LF") (class "Default")
      (node (ref "IC1") (pin "24") (pinfunction "EN2_24") (pintype "bidirectional"))
      (node (ref "IC1") (pin "26") (pinfunction "EN1_26") (pintype "bidirectional"))
      (node (ref "U1") (pin "44") (pinfunction "PE13_44") (pintype "bidirectional"))
    )
    (net (code "25") (name "/M_PWM_RB") (class "Default")
      (node (ref "IC2") (pin "20") (pinfunction "EN4_20") (pintype "bidirectional"))
      (node (ref "IC2") (pin "22") (pinfunction "EN3_22") (pintype "bidirectional"))
      (node (ref "U1") (pin "5") (pinfunction "PE6_5") (pintype "bidirectional"))
    )
    (net (code "26") (name "/M_PWM_RF") (class "Default")
      (node (ref "IC2") (pin "24") (pinfunction "EN2_24") (pintype "bidirectional"))
      (node (ref "IC2") (pin "26") (pinfunction "EN1_26") (pintype "bidirectional"))
      (node (ref "U1") (pin "4") (pinfunction "PE5_4") (pintype "bidirectional"))
    )
    (net (code "27") (name "/M_RB_IN1") (class "Default")
      (node (ref "IC2") (pin "23") (pinfunction "IN3_23") (pintype "input"))
      (node (ref "U1") (pin "88") (pinfunction "PD7_88") (pintype "bidirectional"))
    )
    (net (code "28") (name "/M_RB_IN2") (class "Default")
      (node (ref "IC2") (pin "21") (pinfunction "IN4_21") (pintype "input"))
      (node (ref "U1") (pin "89") (pinfunction "PB3_89") (pintype "bidirectional"))
    )
    (net (code "29") (name "/M_RF_IN1") (class "Default")
      (node (ref "IC2") (pin "27") (pinfunction "IN1_27") (pintype "input"))
      (node (ref "U1") (pin "86") (pinfunction "PD5_86") (pintype "bidirectional"))
    )
    (net (code "30") (name "/M_RF_IN2") (class "Default")
      (node (ref "IC2") (pin "25") (pinfunction "IN2_25") (pintype "input"))
      (node (ref "U1") (pin "87") (pinfunction "PD6_87") (pintype "bidirectional"))
    )
    (net (code "31") (name "/M_SLEEP") (class "Default")
      (node (ref "IC1") (pin "17") (pinfunction "NSLEEP_17") (pintype "bidirectional"))
      (node (ref "IC2") (pin "17") (pinfunction "NSLEEP_17") (pintype "bidirectional"))
      (node (ref "U1") (pin "90") (pinfunction "PB4_90") (pintype "bidirectional"))
    )
    (net (code "32") (name "/NFAULT") (class "Default")
      (node (ref "IC1") (pin "18") (pinfunction "NFAULT_18") (pintype "bidirectional"))
      (node (ref "IC2") (pin "18") (pinfunction "NFAULT_18") (pintype "bidirectional"))
      (node (ref "R20") (pin "1") (pinfunction "1_1") (pintype "passive"))
      (node (ref "U1") (pin "80") (pinfunction "PC12_80") (pintype "bidirectional"))
    )
    (net (code "33") (name "/NRST") (class "Default")
      (node (ref "C28") (pin "1") (pinfunction "1_1") (pintype "passive"))
      (node (ref "R8") (pin "1") (pinfunction "1_1") (pintype "passive"))
      (node (ref "RPI_ZERO") (pin "26") (pinfunction "26_26") (pintype "passive"))
      (node (ref "U1") (pin "14") (pinfunction "NRST_14") (pintype "bidirectional"))
    )
    (net (code "34") (name "/PWM1") (class "Default")
      (node (ref "U1") (pin "47") (pinfunction "PB10_47") (pintype "bidirectional"))
    )
    (net (code "35") (name "/PWM2") (class "Default")
      (node (ref "U1") (pin "48") (pinfunction "PB11_48") (pintype "bidirectional"))
    )
    (net (code "36") (name "/PWM3") (class "Default")
      (node (ref "U1") (pin "35") (pinfunction "PB0_35") (pintype "bidirectional"))
    )
    (net (code "37") (name "/PWM4") (class "Default")
      (node (ref "U1") (pin "36") (pinfunction "PB1_36") (pintype "bidirectional"))
    )
    (net (code "38") (name "/PWM_FAN") (class "Default")
      (node (ref "R22") (pin "1") (pinfunction "1_1") (pintype "passive"))
      (node (ref "U1") (pin "96") (pinfunction "PB9_96") (pintype "bidirectional"))
    )
    (net (code "39") (name "/PWM_LIDAR") (class "Default")
      (node (ref "R38") (pin "1") (pinfunction "1_1") (pintype "passive"))
      (node (ref "U1") (pin "95") (pinfunction "PB8_95") (pintype "bidirectional"))
    )
    (net (code "40") (name "/PWM_LIGHT") (class "Default")
      (node (ref "R6") (pin "1") (pinfunction "1_1") (pintype "passive"))
      (node (ref "U1") (pin "40") (pinfunction "PE9_40") (pintype "bidirectional"))
    )
    (net (code "41") (name "/SWCLK") (class "Default")
      (node (ref "RPI_ZERO") (pin "20") (pinfunction "20_20") (pintype "passive"))
      (node (ref "U1") (pin "76") (pinfunction "PA14_76") (pintype "bidirectional"))
    )
    (net (code "42") (name "/SWDIO") (class "Default")
      (node (ref "RPI_ZERO") (pin "24") (pinfunction "24_24") (pintype "passive"))
      (node (ref "U1") (pin "72") (pinfunction "PA13_72") (pintype "bidirectional"))
    )
    (net (code "43") (name "/TEMPERATURE") (class "Default")
      (node (ref "R25") (pin "1") (pinfunction "1_1") (pintype "passive"))
      (node (ref "U1") (pin "42") (pinfunction "PE11_42") (pintype "bidirectional"))
      (node (ref "U5") (pin "1") (pinfunction "DQ_1") (pintype "bidirectional"))
    )
    (net (code "44") (name "/UART2_RX") (class "Default")
      (node (ref "U1") (pin "26") (pinfunction "PA3_26") (pintype "bidirectional"))
    )
    (net (code "45") (name "/UART2_TX") (class "Default")
      (node (ref "U1") (pin "25") (pinfunction "PA2_25") (pintype "bidirectional"))
    )
    (net (code "46") (name "/UART3_RX") (class "Default")
      (node (ref "U1") (pin "56") (pinfunction "PD9_56") (pintype "bidirectional"))
    )
    (net (code "47") (name "/UART3_TX") (class "Default")
      (node (ref "U1") (pin "55") (pinfunction "PD8_55") (pintype "bidirectional"))
    )
    (net (code "48") (name "/UART4_RX") (class "Default")
      (node (ref "RPI_ZERO") (pin "34") (pinfunction "34_34") (pintype "passive"))
      (node (ref "U1") (pin "79") (pinfunction "PC11_79") (pintype "bidirectional"))
    )
    (net (code "49") (name "/UART4_TX") (class "Default")
      (node (ref "RPI_ZERO") (pin "32") (pinfunction "32_32") (pintype "passive"))
      (node (ref "U1") (pin "78") (pinfunction "PC10_78") (pintype "bidirectional"))
    )
    (net (code "50") (name "/USART3_RX") (class "Default")
      (node (ref "LDIAR") (pin "P1") (pinfunction "1_P1") (pintype "bidirectional"))
    )
    (net (code "51") (name "/USART3_TX") (class "Default")
      (node (ref "LDIAR") (pin "P2") (pinfunction "2_P2") (pintype "bidirectional"))
    )
    (net (code "52") (name "/USB_OTG_DM") (class "Default")
      (node (ref "R14") (pin "1") (pinfunction "1_1") (pintype "passive"))
      (node (ref "U1") (pin "70") (pinfunction "PA11_70") (pintype "bidirectional"))
    )
    (net (code "53") (name "/USB_OTG_DP") (class "Default")
      (node (ref "R18") (pin "1") (pinfunction "1_1") (pintype "passive"))
      (node (ref "U1") (pin "71") (pinfunction "PA12_71") (pintype "bidirectional"))
    )
    (net (code "54") (name "/USB_OTG_ID") (class "Default")
      (node (ref "R16") (pin "1") (pinfunction "1_1") (pintype "passive"))
      (node (ref "U1") (pin "69") (pinfunction "PA10_69") (pintype "bidirectional"))
    )
    (net (code "55") (name "/USB_OTG_VBUS") (class "Default")
      (node (ref "U1") (pin "68") (pinfunction "PA9_68") (pintype "bidirectional"))
    )
    (net (code "57") (name "GND") (class "Default")
      (node (ref "1.8V_CONV") (pin "1") (pinfunction "GND_1") (pintype "passive"))
      (node (ref "3.3V_CONV") (pin "1") (pinfunction "GND_1") (pintype "power_in"))
      (node (ref "5V_CONV") (pin "IN-") (pinfunction "IN-_IN-") (pintype "bidirectional"))
      (node (ref "5V_CONV") (pin "OUT-") (pinfunction "OUT-_OUT-") (pintype "bidirectional"))
      (node (ref "C10") (pin "-") (pinfunction "-_-") (pintype "passive"))
      (node (ref "C11") (pin "1") (pinfunction "1_1") (pintype "passive"))
      (node (ref "C12") (pin "1") (pinfunction "1_1") (pintype "passive"))
      (node (ref "C13") (pin "2") (pinfunction "2_2") (pintype "passive"))
      (node (ref "C14") (pin "2") (pinfunction "2_2") (pintype "passive"))
      (node (ref "C15") (pin "2") (pinfunction "2_2") (pintype "passive"))
      (node (ref "C16") (pin "2") (pinfunction "2_2") (pintype "passive"))
      (node (ref "C17") (pin "2") (pinfunction "2_2") (pintype "passive"))
      (node (ref "C23") (pin "2") (pinfunction "2_2") (pintype "passive"))
      (node (ref "C24") (pin "2") (pinfunction "2_2") (pintype "passive"))
      (node (ref "C25") (pin "2") (pinfunction "2_2") (pintype "passive"))
      (node (ref "C26") (pin "-") (pinfunction "-_-") (pintype "passive"))
      (node (ref "C27") (pin "-") (pinfunction "-_-") (pintype "passive"))
      (node (ref "C28") (pin "2") (pinfunction "2_2") (pintype "passive"))
      (node (ref "C29") (pin "1") (pinfunction "1_1") (pintype "passive"))
      (node (ref "C32") (pin "1") (pinfunction "1_1") (pintype "passive"))
      (node (ref "C34") (pin "-") (pinfunction "-_-") (pintype "passive"))
      (node (ref "C35") (pin "2") (pinfunction "2_2") (pintype "passive"))
      (node (ref "C4") (pin "2") (pinfunction "2_2") (pintype "passive"))
      (node (ref "C41") (pin "2") (pinfunction "2_2") (pintype "passive"))
      (node (ref "C42") (pin "2") (pinfunction "2_2") (pintype "passive"))
      (node (ref "C43") (pin "-") (pinfunction "-_-") (pintype "passive"))
      (node (ref "C44") (pin "2") (pinfunction "2_2") (pintype "passive"))
      (node (ref "C45") (pin "2") (pinfunction "2_2") (pintype "passive"))
      (node (ref "C46") (pin "2") (pinfunction "2_2") (pintype "passive"))
      (node (ref "C47") (pin "2") (pinfunction "2_2") (pintype "passive"))
      (node (ref "C48") (pin "-") (pinfunction "-_-") (pintype "passive"))
      (node (ref "C49") (pin "2") (pinfunction "2_2") (pintype "passive"))
      (node (ref "C5") (pin "-") (pinfunction "-_-") (pintype "passive"))
      (node (ref "C50") (pin "2") (pinfunction "2_2") (pintype "passive"))
      (node (ref "C51") (pin "2") (pinfunction "2_2") (pintype "passive"))
      (node (ref "C6") (pin "2") (pinfunction "2_2") (pintype "passive"))
      (node (ref "C7") (pin "2") (pinfunction "2_2") (pintype "passive"))
      (node (ref "C8") (pin "2") (pinfunction "2_2") (pintype "passive"))
      (node (ref "GND") (pin "TP") (pinfunction "TP_TP") (pintype "input"))
      (node (ref "I2C") (pin "3") (pinfunction "3_3") (pintype "passive"))
      (node (ref "IC1") (pin "14") (pinfunction "VNEG_3_14") (pintype "bidirectional"))
      (node (ref "IC1") (pin "19") (pinfunction "LGND_19") (pintype "power_in"))
      (node (ref "IC1") (pin "28") (pinfunction "VNEG_4_28") (pintype "bidirectional"))
      (node (ref "IC1") (pin "29") (pinfunction "EP_29") (pintype "power_in"))
      (node (ref "IC1") (pin "6") (pinfunction "VNEG_1_6") (pintype "bidirectional"))
      (node (ref "IC1") (pin "9") (pinfunction "VNEG_2_9") (pintype "bidirectional"))
      (node (ref "IC2") (pin "14") (pinfunction "VNEG_3_14") (pintype "bidirectional"))
      (node (ref "IC2") (pin "19") (pinfunction "LGND_19") (pintype "power_in"))
      (node (ref "IC2") (pin "28") (pinfunction "VNEG_4_28") (pintype "bidirectional"))
      (node (ref "IC2") (pin "29") (pinfunction "EP_29") (pintype "power_in"))
      (node (ref "IC2") (pin "6") (pinfunction "VNEG_1_6") (pintype "bidirectional"))
      (node (ref "IC2") (pin "9") (pinfunction "VNEG_2_9") (pintype "bidirectional"))
      (node (ref "INA219") (pin "3") (pinfunction "GND_3") (pintype "bidirectional"))
      (node (ref "INA219") (pin "7") (pinfunction "A0_7") (pintype "bidirectional"))
      (node (ref "INA219") (pin "8") (pinfunction "A1_8") (pintype "bidirectional"))
      (node (ref "J1") (pin "5") (pinfunction "5_5") (pintype "passive"))
      (node (ref "LDIAR") (pin "P4") (pinfunction "4_P4") (pintype "bidirectional"))
      (node (ref "LED1") (pin "1") (pinfunction "K_1") (pintype "bidirectional"))
      (node (ref "M1") (pin "2") (pinfunction "S_2") (pintype "passive"))
      (node (ref "M2") (pin "2") (pinfunction "S_2") (pintype "passive"))
      (node (ref "M3") (pin "2") (pinfunction "S_2") (pintype "passive"))
      (node (ref "P1") (pin "5") (pinfunction "5_5") (pintype "passive"))
      (node (ref "P2") (pin "5") (pinfunction "5_5") (pintype "passive"))
      (node (ref "P3") (pin "5") (pinfunction "5_5") (pintype "passive"))
      (node (ref "P4") (pin "5") (pinfunction "5_5") (pintype "passive"))
      (node (ref "PCA9533") (pin "4") (pinfunction "VSS_4") (pintype "power_in"))
      (node (ref "PWR") (pin "2") (pinfunction "2_2") (pintype "passive"))
      (node (ref "R11") (pin "1") (pinfunction "1_1") (pintype "passive"))
      (node (ref "R13") (pin "1") (pinfunction "1_1") (pintype "passive"))
      (node (ref "R19") (pin "1") (pinfunction "1_1") (pintype "passive"))
      (node (ref "R35") (pin "1") (pinfunction "1_1") (pintype "passive"))
      (node (ref "R7") (pin "2") (pinfunction "2_2") (pintype "passive"))
      (node (ref "R9") (pin "1") (pinfunction "1_1") (pintype "passive"))
      (node (ref "RPI_ZERO") (pin "1") (pinfunction "1_1") (pintype "passive"))
      (node (ref "RPI_ZERO") (pin "12") (pinfunction "12_12") (pintype "passive"))
      (node (ref "RPI_ZERO") (pin "15") (pinfunction "15_15") (pintype "passive"))
      (node (ref "RPI_ZERO") (pin "22") (pinfunction "22_22") (pintype "passive"))
      (node (ref "RPI_ZERO") (pin "28") (pinfunction "28_28") (pintype "passive"))
      (node (ref "RPI_ZERO") (pin "31") (pinfunction "31_31") (pintype "passive"))
      (node (ref "RPI_ZERO") (pin "36") (pinfunction "36_36") (pintype "passive"))
      (node (ref "RPI_ZERO") (pin "8") (pinfunction "8_8") (pintype "passive"))
      (node (ref "U1") (pin "10") (pinfunction "VSS_10") (pintype "power_in"))
      (node (ref "U1") (pin "20") (pinfunction "VSSA_20") (pintype "power_in"))
      (node (ref "U1") (pin "27") (pinfunction "VSS_27") (pintype "power_in"))
      (node (ref "U1") (pin "74") (pinfunction "VSS_74") (pintype "power_in"))
      (node (ref "U1") (pin "99") (pinfunction "VSS_99") (pintype "power_in"))
      (node (ref "U3") (pin "18") (pinfunction "GND_18") (pintype "power_in"))
      (node (ref "U5") (pin "4") (pinfunction "GND_4") (pintype "power_in"))
    )
    (net (code "58") (name "Net-(D2-A)") (class "Default")
      (node (ref "D2") (pin "2") (pinfunction "A_2") (pintype "bidirectional"))
      (node (ref "J1") (pin "1") (pinfunction "1_1") (pintype "passive"))
    )
    (net (code "59") (name "Net-(FAN-2)") (class "Default")
      (node (ref "D3") (pin "A") (pinfunction "A_A") (pintype "passive"))
      (node (ref "FAN") (pin "P2") (pinfunction "2_P2") (pintype "bidirectional"))
      (node (ref "M2") (pin "3") (pinfunction "D_3") (pintype "passive"))
    )
    (net (code "60") (name "Net-(FRONTLIGHT-1)") (class "Default")
      (node (ref "FRONTLIGHT") (pin "P1") (pinfunction "1_P1") (pintype "bidirectional"))
      (node (ref "R3") (pin "2") (pinfunction "2_2") (pintype "passive"))
    )
    (net (code "61") (name "Net-(FRONTLIGHT-2)") (class "Default")
      (node (ref "FRONTLIGHT") (pin "P2") (pinfunction "2_P2") (pintype "bidirectional"))
      (node (ref "M3") (pin "3") (pinfunction "D_3") (pintype "passive"))
    )
    (net (code "62") (name "Net-(IC1-CP1)") (class "Default")
      (node (ref "C2") (pin "1") (pinfunction "1_1") (pintype "passive"))
      (node (ref "IC1") (pin "1") (pinfunction "CP1_1") (pintype "bidirectional"))
    )
    (net (code "63") (name "Net-(IC1-CP2)") (class "Default")
      (node (ref "C2") (pin "2") (pinfunction "2_2") (pintype "passive"))
      (node (ref "IC1") (pin "2") (pinfunction "CP2_2") (pintype "bidirectional"))
    )
    (net (code "64") (name "Net-(IC1-OUT1)") (class "Default")
      (node (ref "IC1") (pin "5") (pinfunction "OUT1_5") (pintype "output"))
      (node (ref "P3") (pin "1") (pinfunction "1_1") (pintype "passive"))
    )
    (net (code "65") (name "Net-(IC1-OUT2)") (class "Default")
      (node (ref "IC1") (pin "7") (pinfunction "OUT2_7") (pintype "output"))
      (node (ref "P3") (pin "6") (pinfunction "6_6") (pintype "passive"))
    )
    (net (code "66") (name "Net-(IC1-OUT3)") (class "Default")
      (node (ref "IC1") (pin "8") (pinfunction "OUT3_8") (pintype "output"))
      (node (ref "P1") (pin "1") (pinfunction "1_1") (pintype "passive"))
    )
    (net (code "67") (name "Net-(IC1-OUT4)") (class "Default")
      (node (ref "IC1") (pin "10") (pinfunction "OUT4_10") (pintype "output"))
      (node (ref "P1") (pin "6") (pinfunction "6_6") (pintype "passive"))
    )
    (net (code "68") (name "Net-(IC1-V3P3OUT)") (class "Default")
      (node (ref "C4") (pin "1") (pinfunction "1_1") (pintype "passive"))
      (node (ref "IC1") (pin "15") (pinfunction "V3P3OUT_15") (pintype "output"))
    )
    (net (code "69") (name "Net-(IC1-VCP)") (class "Default")
      (node (ref "C3") (pin "1") (pinfunction "1_1") (pintype "passive"))
      (node (ref "IC1") (pin "3") (pinfunction "VCP_3") (pintype "bidirectional"))
    )
    (net (code "70") (name "Net-(IC2-CP1)") (class "Default")
      (node (ref "C21") (pin "1") (pinfunction "1_1") (pintype "passive"))
      (node (ref "IC2") (pin "1") (pinfunction "CP1_1") (pintype "bidirectional"))
    )
    (net (code "71") (name "Net-(IC2-CP2)") (class "Default")
      (node (ref "C21") (pin "2") (pinfunction "2_2") (pintype "passive"))
      (node (ref "IC2") (pin "2") (pinfunction "CP2_2") (pintype "bidirectional"))
    )
    (net (code "72") (name "Net-(IC2-OUT1)") (class "Default")
      (node (ref "IC2") (pin "5") (pinfunction "OUT1_5") (pintype "output"))
      (node (ref "P4") (pin "1") (pinfunction "1_1") (pintype "passive"))
    )
    (net (code "73") (name "Net-(IC2-OUT2)") (class "Default")
      (node (ref "IC2") (pin "7") (pinfunction "OUT2_7") (pintype "output"))
      (node (ref "P4") (pin "6") (pinfunction "6_6") (pintype "passive"))
    )
    (net (code "74") (name "Net-(IC2-OUT3)") (class "Default")
      (node (ref "IC2") (pin "8") (pinfunction "OUT3_8") (pintype "output"))
      (node (ref "P2") (pin "1") (pinfunction "1_1") (pintype "passive"))
    )
    (net (code "75") (name "Net-(IC2-OUT4)") (class "Default")
      (node (ref "IC2") (pin "10") (pinfunction "OUT4_10") (pintype "output"))
      (node (ref "P2") (pin "6") (pinfunction "6_6") (pintype "passive"))
    )
    (net (code "76") (name "Net-(IC2-V3P3OUT)") (class "Default")
      (node (ref "C25") (pin "1") (pinfunction "1_1") (pintype "passive"))
      (node (ref "IC2") (pin "15") (pinfunction "V3P3OUT_15") (pintype "output"))
    )
    (net (code "77") (name "Net-(IC2-VCP)") (class "Default")
      (node (ref "C22") (pin "1") (pinfunction "1_1") (pintype "passive"))
      (node (ref "IC2") (pin "3") (pinfunction "VCP_3") (pintype "bidirectional"))
    )
    (net (code "78") (name "Net-(J1-Pad2)") (class "Default")
      (node (ref "J1") (pin "2") (pinfunction "2_2") (pintype "passive"))
      (node (ref "R14") (pin "2") (pinfunction "2_2") (pintype "passive"))
    )
    (net (code "79") (name "Net-(J1-Pad3)") (class "Default")
      (node (ref "J1") (pin "3") (pinfunction "3_3") (pintype "passive"))
      (node (ref "R12") (pin "1") (pinfunction "1_1") (pintype "passive"))
      (node (ref "R18") (pin "2") (pinfunction "2_2") (pintype "passive"))
    )
    (net (code "80") (name "Net-(J1-Pad4)") (class "Default")
      (node (ref "J1") (pin "4") (pinfunction "4_4") (pintype "passive"))
      (node (ref "R16") (pin "2") (pinfunction "2_2") (pintype "passive"))
    )
    (net (code "81") (name "Net-(J1-SHIELD-PadSH1)") (class "Default")
      (node (ref "J1") (pin "SH1") (pinfunction "SHIELD_SH1") (pintype "passive"))
      (node (ref "J1") (pin "SH2") (pinfunction "SHIELD_SH2") (pintype "passive"))
      (node (ref "J1") (pin "SH3") (pinfunction "SHIELD_SH3") (pintype "passive"))
      (node (ref "J1") (pin "SH4") (pinfunction "SHIELD_SH4") (pintype "passive"))
      (node (ref "J1") (pin "SH5") (pinfunction "SHIELD_SH5") (pintype "passive"))
      (node (ref "R19") (pin "2") (pinfunction "2_2") (pintype "passive"))
    )
    (net (code "82") (name "Net-(LED1-A)") (class "Default")
      (node (ref "LED1") (pin "2") (pinfunction "A_2") (pintype "bidirectional"))
      (node (ref "R5") (pin "1") (pinfunction "1_1") (pintype "passive"))
    )
    (net (code "83") (name "Net-(LIDAR_MOTOR-2)") (class "Default")
      (node (ref "D1") (pin "A") (pinfunction "A_A") (pintype "passive"))
      (node (ref "LIDAR_MOTOR") (pin "P2") (pinfunction "2_P2") (pintype "bidirectional"))
      (node (ref "M1") (pin "3") (pinfunction "D_3") (pintype "passive"))
    )
    (net (code "84") (name "Net-(M1-G)") (class "Default")
      (node (ref "M1") (pin "1") (pinfunction "G_1") (pintype "passive"))
      (node (ref "R38") (pin "2") (pinfunction "2_2") (pintype "passive"))
      (node (ref "R9") (pin "2") (pinfunction "2_2") (pintype "passive"))
    )
    (net (code "85") (name "Net-(M2-G)") (class "Default")
      (node (ref "M2") (pin "1") (pinfunction "G_1") (pintype "passive"))
      (node (ref "R13") (pin "2") (pinfunction "2_2") (pintype "passive"))
      (node (ref "R22") (pin "2") (pinfunction "2_2") (pintype "passive"))
    )
    (net (code "86") (name "Net-(M3-G)") (class "Default")
      (node (ref "M3") (pin "1") (pinfunction "G_1") (pintype "passive"))
      (node (ref "R11") (pin "2") (pinfunction "2_2") (pintype "passive"))
      (node (ref "R6") (pin "2") (pinfunction "2_2") (pintype "passive"))
    )
    (net (code "87") (name "Net-(P1-Pad2)") (class "Default")
      (node (ref "P1") (pin "2") (pinfunction "2_2") (pintype "passive"))
      (node (ref "P2") (pin "2") (pinfunction "2_2") (pintype "passive"))
      (node (ref "P3") (pin "2") (pinfunction "2_2") (pintype "passive"))
      (node (ref "P4") (pin "2") (pinfunction "2_2") (pintype "passive"))
      (node (ref "SJ1") (pin "2") (pinfunction "2_2") (pintype "passive"))
    )
    (net (code "88") (name "Net-(PCA9533-LED0)") (class "Default")
      (node (ref "PCA9533") (pin "1") (pinfunction "LED0_1") (pintype "bidirectional"))
      (node (ref "R28") (pin "1") (pinfunction "1_1") (pintype "passive"))
    )
    (net (code "89") (name "Net-(PCA9533-LED1)") (class "Default")
      (node (ref "PCA9533") (pin "2") (pinfunction "LED1_2") (pintype "bidirectional"))
      (node (ref "R27") (pin "1") (pinfunction "1_1") (pintype "passive"))
    )
    (net (code "90") (name "Net-(PCA9533-LED2)") (class "Default")
      (node (ref "PCA9533") (pin "3") (pinfunction "LED2_3") (pintype "bidirectional"))
      (node (ref "R26") (pin "1") (pinfunction "1_1") (pintype "passive"))
    )
    (net (code "91") (name "Net-(RGB_LED-2)") (class "Default")
      (node (ref "R28") (pin "2") (pinfunction "2_2") (pintype "passive"))
      (node (ref "RGB_LED") (pin "P2") (pinfunction "2_P2") (pintype "bidirectional"))
    )
    (net (code "92") (name "Net-(RGB_LED-3)") (class "Default")
      (node (ref "R27") (pin "2") (pinfunction "2_2") (pintype "passive"))
      (node (ref "RGB_LED") (pin "P3") (pinfunction "3_P3") (pintype "bidirectional"))
    )
    (net (code "93") (name "Net-(RGB_LED-4)") (class "Default")
      (node (ref "R26") (pin "2") (pinfunction "2_2") (pintype "passive"))
      (node (ref "RGB_LED") (pin "P4") (pinfunction "4_P4") (pintype "bidirectional"))
    )
    (net (code "94") (name "Net-(U1-BOOT0)") (class "Default")
      (node (ref "R7") (pin "1") (pinfunction "1_1") (pintype "passive"))
      (node (ref "U1") (pin "94") (pinfunction "BOOT0_94") (pintype "input"))
    )
    (net (code "95") (name "Net-(U1-PH0)") (class "Default")
      (node (ref "R15") (pin "1") (pinfunction "1_1") (pintype "passive"))
      (node (ref "U1") (pin "12") (pinfunction "PH0_12") (pintype "bidirectional"))
    )
    (net (code "96") (name "Net-(U1-PH1)") (class "Default")
      (node (ref "C11") (pin "2") (pinfunction "2_2") (pintype "passive"))
      (node (ref "U1") (pin "13") (pinfunction "PH1_13") (pintype "bidirectional"))
      (node (ref "X1") (pin "1") (pinfunction "1_1") (pintype "passive"))
    )
    (net (code "97") (name "Net-(U1-VCAP_1)") (class "Default")
      (node (ref "C29") (pin "2") (pinfunction "2_2") (pintype "passive"))
      (node (ref "U1") (pin "49") (pinfunction "VCAP_1_49") (pintype "power_in"))
    )
    (net (code "98") (name "Net-(U1-VCAP_2)") (class "Default")
      (node (ref "C32") (pin "2") (pinfunction "2_2") (pintype "passive"))
      (node (ref "U1") (pin "73") (pinfunction "VCAP_2_73") (pintype "power_in"))
    )
    (net (code "99") (name "Net-(U3-REGOUT)") (class "Default")
      (node (ref "C7") (pin "1") (pinfunction "1_1") (pintype "passive"))
      (node (ref "U3") (pin "10") (pinfunction "REGOUT_10") (pintype "output"))
    )
    (net (code "100") (name "Net-(X1-2)") (class "Default")
      (node (ref "C12") (pin "2") (pinfunction "2_2") (pintype "passive"))
      (node (ref "R15") (pin "2") (pinfunction "2_2") (pintype "passive"))
      (node (ref "X1") (pin "3") (pinfunction "2_3") (pintype "passive"))
    )
    (net (code "101") (name "V+") (class "Default")
      (node (ref "C16") (pin "1") (pinfunction "1_1") (pintype "passive"))
      (node (ref "C27") (pin "+") (pinfunction "+_+") (pintype "passive"))
      (node (ref "INA219") (pin "1") (pinfunction "VIN+_1") (pintype "bidirectional"))
      (node (ref "PWR") (pin "1") (pinfunction "1_1") (pintype "passive"))
      (node (ref "R17") (pin "2") (pinfunction "2_2") (pintype "passive"))
      (node (ref "R34") (pin "2") (pinfunction "2_2") (pintype "passive"))
    )
    (net (code "102") (name "unconnected-(IC1-NC_1-Pad12)") (class "Default")
      (node (ref "IC1") (pin "12") (pinfunction "NC_1_12") (pintype "bidirectional"))
    )
    (net (code "103") (name "unconnected-(IC1-NC_2-Pad13)") (class "Default")
      (node (ref "IC1") (pin "13") (pinfunction "NC_2_13") (pintype "bidirectional"))
    )
    (net (code "104") (name "unconnected-(IC2-NC_1-Pad12)") (class "Default")
      (node (ref "IC2") (pin "12") (pinfunction "NC_1_12") (pintype "bidirectional"))
    )
    (net (code "105") (name "unconnected-(IC2-NC_2-Pad13)") (class "Default")
      (node (ref "IC2") (pin "13") (pinfunction "NC_2_13") (pintype "bidirectional"))
    )
    (net (code "106") (name "unconnected-(PCA9533-LED3-Pad5)") (class "Default")
      (node (ref "PCA9533") (pin "5") (pinfunction "LED3_5") (pintype "bidirectional"))
    )
    (net (code "107") (name "unconnected-(RPI_ZERO-Pad2)") (class "Default")
      (node (ref "RPI_ZERO") (pin "2") (pinfunction "2_2") (pintype "passive"))
    )
    (net (code "108") (name "unconnected-(RPI_ZERO-Pad3)") (class "Default")
      (node (ref "RPI_ZERO") (pin "3") (pinfunction "3_3") (pintype "passive"))
    )
    (net (code "109") (name "unconnected-(RPI_ZERO-Pad4)") (class "Default")
      (node (ref "RPI_ZERO") (pin "4") (pinfunction "4_4") (pintype "passive"))
    )
    (net (code "110") (name "unconnected-(RPI_ZERO-Pad5)") (class "Default")
      (node (ref "RPI_ZERO") (pin "5") (pinfunction "5_5") (pintype "passive"))
    )
    (net (code "111") (name "unconnected-(RPI_ZERO-Pad6)") (class "Default")
      (node (ref "RPI_ZERO") (pin "6") (pinfunction "6_6") (pintype "passive"))
    )
    (net (code "112") (name "unconnected-(RPI_ZERO-Pad7)") (class "Default")
      (node (ref "RPI_ZERO") (pin "7") (pinfunction "7_7") (pintype "passive"))
    )
    (net (code "113") (name "unconnected-(RPI_ZERO-Pad9)") (class "Default")
      (node (ref "RPI_ZERO") (pin "9") (pinfunction "9_9") (pintype "passive"))
    )
    (net (code "114") (name "unconnected-(RPI_ZERO-Pad10)") (class "Default")
      (node (ref "RPI_ZERO") (pin "10") (pinfunction "10_10") (pintype "passive"))
    )
    (net (code "115") (name "unconnected-(RPI_ZERO-Pad11)") (class "Default")
      (node (ref "RPI_ZERO") (pin "11") (pinfunction "11_11") (pintype "passive"))
    )
    (net (code "116") (name "unconnected-(RPI_ZERO-Pad13)") (class "Default")
      (node (ref "RPI_ZERO") (pin "13") (pinfunction "13_13") (pintype "passive"))
    )
    (net (code "117") (name "unconnected-(RPI_ZERO-Pad14)") (class "Default")
      (node (ref "RPI_ZERO") (pin "14") (pinfunction "14_14") (pintype "passive"))
    )
    (net (code "118") (name "unconnected-(RPI_ZERO-Pad16)") (class "Default")
      (node (ref "RPI_ZERO") (pin "16") (pinfunction "16_16") (pintype "passive"))
    )
    (net (code "119") (name "unconnected-(RPI_ZERO-Pad17)") (class "Default")
      (node (ref "RPI_ZERO") (pin "17") (pinfunction "17_17") (pintype "passive"))
    )
    (net (code "120") (name "unconnected-(RPI_ZERO-Pad18)") (class "Default")
      (node (ref "RPI_ZERO") (pin "18") (pinfunction "18_18") (pintype "passive"))
    )
    (net (code "121") (name "unconnected-(RPI_ZERO-Pad19)") (class "Default")
      (node (ref "RPI_ZERO") (pin "19") (pinfunction "19_19") (pintype "passive"))
    )
    (net (code "122") (name "unconnected-(RPI_ZERO-Pad21)") (class "Default")
      (node (ref "RPI_ZERO") (pin "21") (pinfunction "21_21") (pintype "passive"))
    )
    (net (code "123") (name "unconnected-(RPI_ZERO-Pad23)") (class "Default")
      (node (ref "RPI_ZERO") (pin "23") (pinfunction "23_23") (pintype "passive"))
    )
    (net (code "124") (name "unconnected-(RPI_ZERO-Pad25)") (class "Default")
      (node (ref "RPI_ZERO") (pin "25") (pinfunction "25_25") (pintype "passive"))
    )
    (net (code "125") (name "unconnected-(RPI_ZERO-Pad27)") (class "Default")
      (node (ref "RPI_ZERO") (pin "27") (pinfunction "27_27") (pintype "passive"))
    )
    (net (code "126") (name "unconnected-(RPI_ZERO-Pad29)") (class "Default")
      (node (ref "RPI_ZERO") (pin "29") (pinfunction "29_29") (pintype "passive"))
    )
    (net (code "127") (name "unconnected-(RPI_ZERO-Pad30)") (class "Default")
      (node (ref "RPI_ZERO") (pin "30") (pinfunction "30_30") (pintype "passive"))
    )
    (net (code "128") (name "unconnected-(RPI_ZERO-Pad33)") (class "Default")
      (node (ref "RPI_ZERO") (pin "33") (pinfunction "33_33") (pintype "passive"))
    )
    (net (code "129") (name "unconnected-(RPI_ZERO-Pad35)") (class "Default")
      (node (ref "RPI_ZERO") (pin "35") (pinfunction "35_35") (pintype "passive"))
    )
    (net (code "130") (name "unconnected-(RPI_ZERO-Pad37)") (class "Default")
      (node (ref "RPI_ZERO") (pin "37") (pinfunction "37_37") (pintype "passive"))
    )
    (net (code "131") (name "unconnected-(RPI_ZERO-Pad39)") (class "Default")
      (node (ref "RPI_ZERO") (pin "39") (pinfunction "39_39") (pintype "passive"))
    )
    (net (code "132") (name "unconnected-(U1-PA4-Pad29)") (class "Default")
      (node (ref "U1") (pin "29") (pinfunction "PA4_29") (pintype "bidirectional"))
    )
    (net (code "133") (name "unconnected-(U1-PA5-Pad30)") (class "Default")
      (node (ref "U1") (pin "30") (pinfunction "PA5_30") (pintype "bidirectional"))
    )
    (net (code "134") (name "unconnected-(U1-PA15-Pad77)") (class "Default")
      (node (ref "U1") (pin "77") (pinfunction "PA15_77") (pintype "bidirectional"))
    )
    (net (code "135") (name "unconnected-(U1-PB2-Pad37)") (class "Default")
      (node (ref "U1") (pin "37") (pinfunction "PB2_37") (pintype "bidirectional"))
    )
    (net (code "136") (name "unconnected-(U1-PB5-Pad91)") (class "Default")
      (node (ref "U1") (pin "91") (pinfunction "PB5_91") (pintype "bidirectional"))
    )
    (net (code "137") (name "unconnected-(U1-PB12-Pad51)") (class "Default")
      (node (ref "U1") (pin "51") (pinfunction "PB12_51") (pintype "bidirectional"))
    )
    (net (code "138") (name "unconnected-(U1-PB13-Pad52)") (class "Default")
      (node (ref "U1") (pin "52") (pinfunction "PB13_52") (pintype "bidirectional"))
    )
    (net (code "139") (name "unconnected-(U1-PB14-Pad53)") (class "Default")
      (node (ref "U1") (pin "53") (pinfunction "PB14_53") (pintype "bidirectional"))
    )
    (net (code "140") (name "unconnected-(U1-PB15-Pad54)") (class "Default")
      (node (ref "U1") (pin "54") (pinfunction "PB15_54") (pintype "bidirectional"))
    )
    (net (code "141") (name "unconnected-(U1-PC1-Pad16)") (class "Default")
      (node (ref "U1") (pin "16") (pinfunction "PC1_16") (pintype "bidirectional"))
    )
    (net (code "142") (name "unconnected-(U1-PC2-Pad17)") (class "Default")
      (node (ref "U1") (pin "17") (pinfunction "PC2_17") (pintype "bidirectional"))
    )
    (net (code "143") (name "unconnected-(U1-PC3-Pad18)") (class "Default")
      (node (ref "U1") (pin "18") (pinfunction "PC3_18") (pintype "bidirectional"))
    )
    (net (code "144") (name "unconnected-(U1-PC4-Pad33)") (class "Default")
      (node (ref "U1") (pin "33") (pinfunction "PC4_33") (pintype "bidirectional"))
    )
    (net (code "145") (name "unconnected-(U1-PC5-Pad34)") (class "Default")
      (node (ref "U1") (pin "34") (pinfunction "PC5_34") (pintype "bidirectional"))
    )
    (net (code "146") (name "unconnected-(U1-PC8-Pad65)") (class "Default")
      (node (ref "U1") (pin "65") (pinfunction "PC8_65") (pintype "bidirectional"))
    )
    (net (code "147") (name "unconnected-(U1-PC13-Pad7)") (class "Default")
      (node (ref "U1") (pin "7") (pinfunction "PC13_7") (pintype "bidirectional"))
    )
    (net (code "148") (name "unconnected-(U1-PC14-Pad8)") (class "Default")
      (node (ref "U1") (pin "8") (pinfunction "PC14_8") (pintype "bidirectional"))
    )
    (net (code "149") (name "unconnected-(U1-PC15-Pad9)") (class "Default")
      (node (ref "U1") (pin "9") (pinfunction "PC15_9") (pintype "bidirectional"))
    )
    (net (code "150") (name "unconnected-(U1-PD10-Pad57)") (class "Default")
      (node (ref "U1") (pin "57") (pinfunction "PD10_57") (pintype "bidirectional"))
    )
    (net (code "151") (name "unconnected-(U1-PD11-Pad58)") (class "Default")
      (node (ref "U1") (pin "58") (pinfunction "PD11_58") (pintype "bidirectional"))
    )
    (net (code "152") (name "unconnected-(U1-PD14-Pad61)") (class "Default")
      (node (ref "U1") (pin "61") (pinfunction "PD14_61") (pintype "bidirectional"))
    )
    (net (code "153") (name "unconnected-(U1-PD15-Pad62)") (class "Default")
      (node (ref "U1") (pin "62") (pinfunction "PD15_62") (pintype "bidirectional"))
    )
    (net (code "154") (name "unconnected-(U1-PE0-Pad97)") (class "Default")
      (node (ref "U1") (pin "97") (pinfunction "PE0_97") (pintype "bidirectional"))
    )
    (net (code "155") (name "unconnected-(U1-PE1-Pad98)") (class "Default")
      (node (ref "U1") (pin "98") (pinfunction "PE1_98") (pintype "bidirectional"))
    )
    (net (code "156") (name "unconnected-(U1-PE2-Pad1)") (class "Default")
      (node (ref "U1") (pin "1") (pinfunction "PE2_1") (pintype "bidirectional"))
    )
    (net (code "157") (name "unconnected-(U1-PE3-Pad2)") (class "Default")
      (node (ref "U1") (pin "2") (pinfunction "PE3_2") (pintype "bidirectional"))
    )
    (net (code "158") (name "unconnected-(U1-PE4-Pad3)") (class "Default")
      (node (ref "U1") (pin "3") (pinfunction "PE4_3") (pintype "bidirectional"))
    )
    (net (code "159") (name "unconnected-(U1-PE7-Pad38)") (class "Default")
      (node (ref "U1") (pin "38") (pinfunction "PE7_38") (pintype "bidirectional"))
    )
    (net (code "160") (name "unconnected-(U1-PE8-Pad39)") (class "Default")
      (node (ref "U1") (pin "39") (pinfunction "PE8_39") (pintype "bidirectional"))
    )
    (net (code "161") (name "unconnected-(U1-PE10-Pad41)") (class "Default")
      (node (ref "U1") (pin "41") (pinfunction "PE10_41") (pintype "bidirectional"))
    )
    (net (code "162") (name "unconnected-(U1-PE12-Pad43)") (class "Default")
      (node (ref "U1") (pin "43") (pinfunction "PE12_43") (pintype "bidirectional"))
    )
    (net (code "163") (name "unconnected-(U1-PE15-Pad46)") (class "Default")
      (node (ref "U1") (pin "46") (pinfunction "PE15_46") (pintype "bidirectional"))
    )
    (net (code "164") (name "unconnected-(U3-AD0{slash}SDO-Pad9)") (class "Default")
      (node (ref "U3") (pin "9") (pinfunction "AD0/SDO_9") (pintype "output"))
    )
    (net (code "165") (name "unconnected-(U3-AUX_CL-Pad7)") (class "Default")
      (node (ref "U3") (pin "7") (pinfunction "AUX_CL_7") (pintype "input"))
    )
    (net (code "166") (name "unconnected-(U3-AUX_DA-Pad21)") (class "Default")
      (node (ref "U3") (pin "21") (pinfunction "AUX_DA_21") (pintype "input"))
    )
    (net (code "167") (name "unconnected-(U3-FSYNC-Pad11)") (class "Default")
      (node (ref "U3") (pin "11") (pinfunction "FSYNC_11") (pintype "input"))
    )
    (net (code "168") (name "unconnected-(U3-INT1-Pad12)") (class "Default")
      (node (ref "U3") (pin "12") (pinfunction "INT1_12") (pintype "output"))
    )
    (net (code "169") (name "unconnected-(U3-NCS-Pad22)") (class "Default")
      (node (ref "U3") (pin "22") (pinfunction "NCS_22") (pintype "input"))
    )
    (net (code "170") (name "unconnected-(U3-RESV_19-Pad19)") (class "Default")
      (node (ref "U3") (pin "19") (pinfunction "RESV_19_19") (pintype "passive"))
    )
    (net (code "171") (name "unconnected-(U3-RESV_20-Pad20)") (class "Default")
      (node (ref "U3") (pin "20") (pinfunction "RESV_20_20") (pintype "passive"))
    )
  )
)
